# ltc4063-test.net
KiCad netlist of a schematic drawn in EAGLE
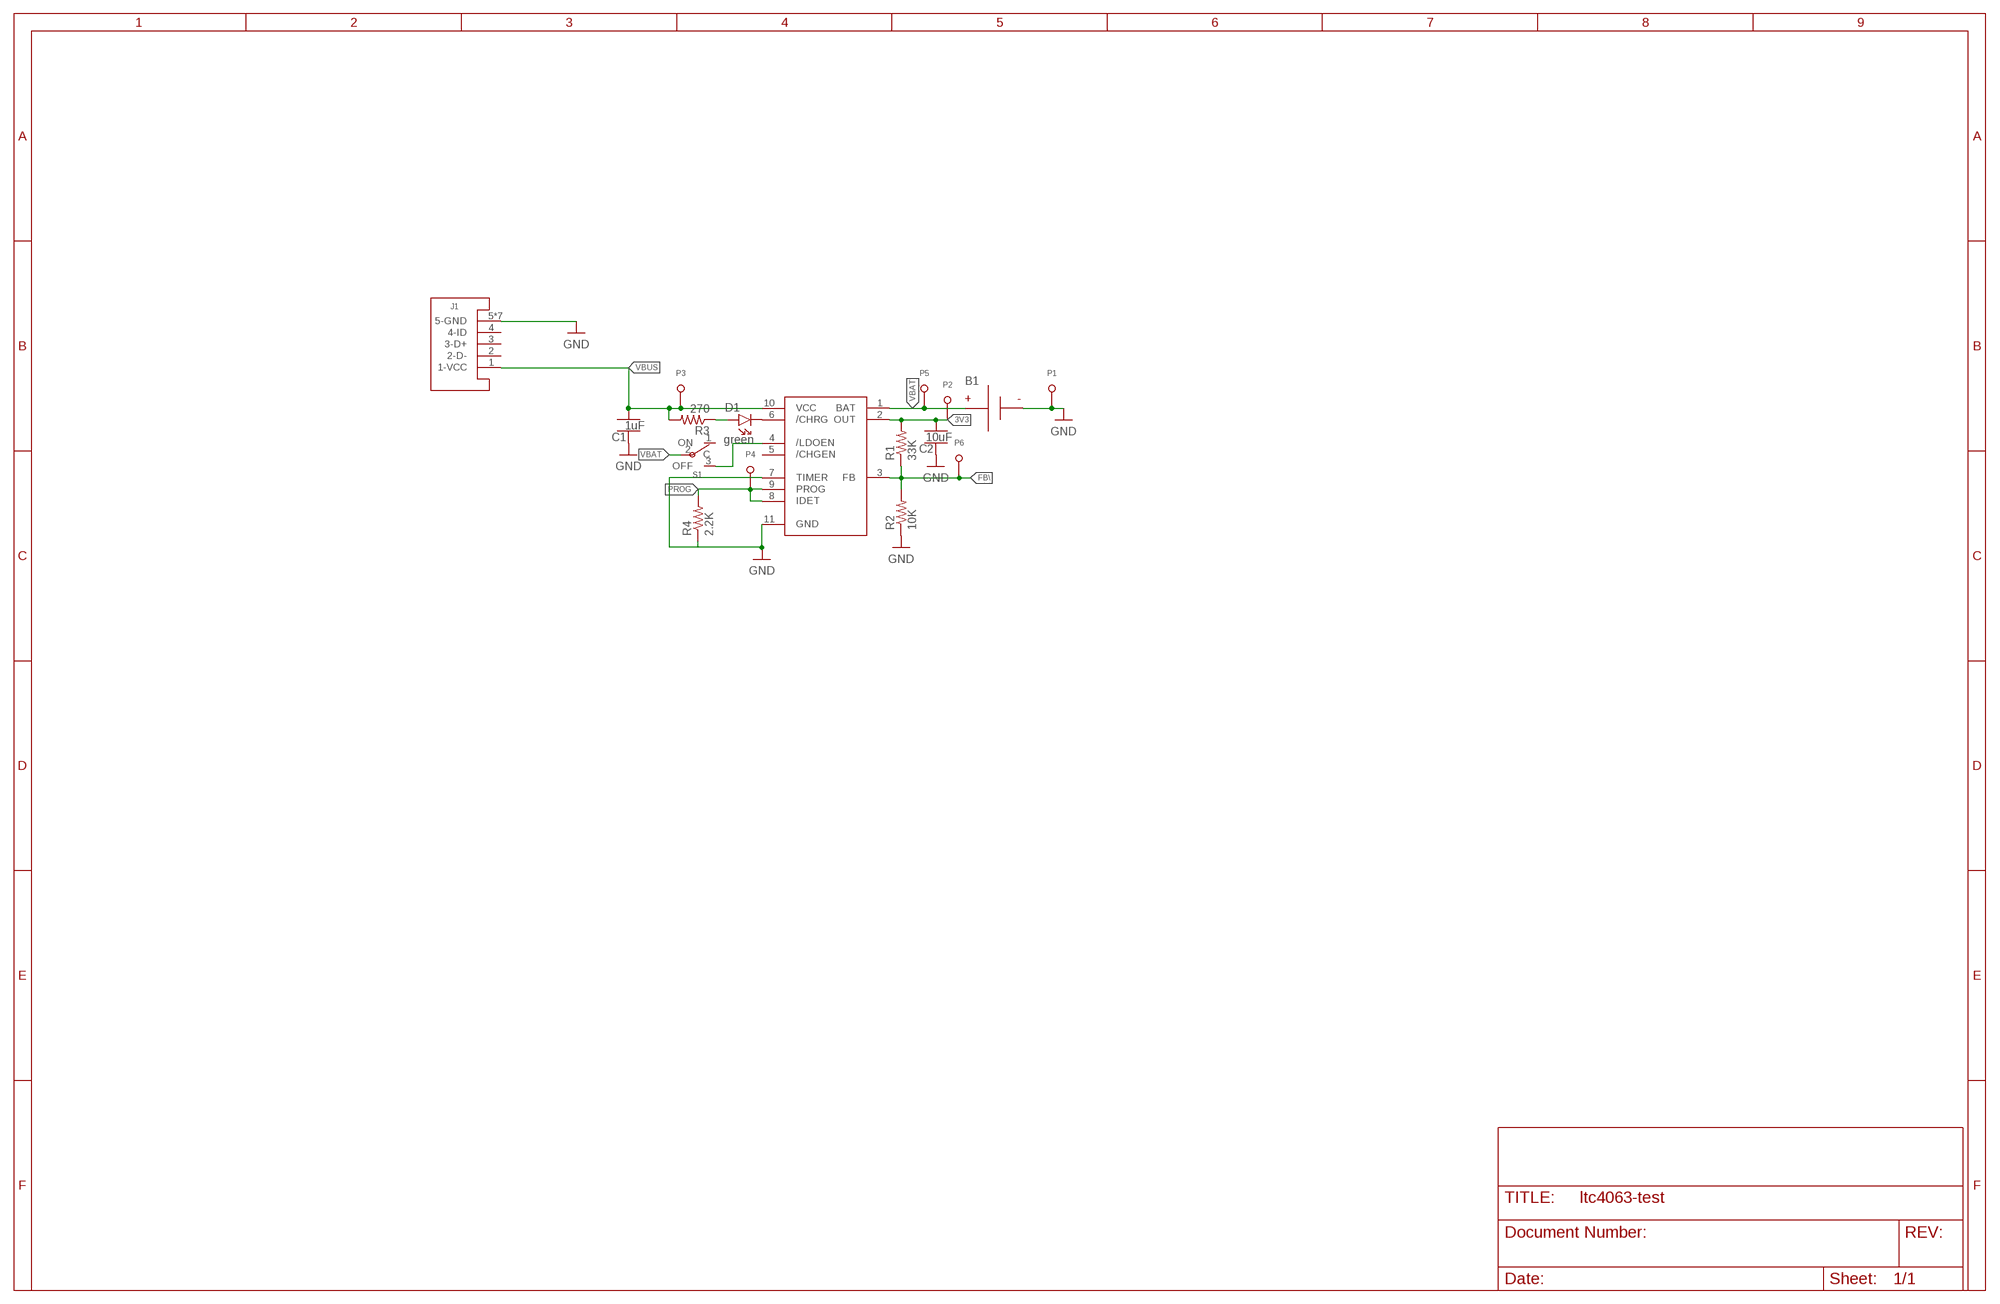
[diagram p0: schematic, sheet 1]

(export (version "E")
  (design (tool "Eeschema 10.0.6"))
  (components
    (comp (ref "B1")
      (value "BATTERY-SPRING-SMD")
      (footprint "eagle-import:WIRE-TERMINAL-1X2-2.5MM-SMD-AVX-009276002021106")
      (fields (field (name "CREATOR") "Swanson"))
      (libsource (lib "eagle-import") (part "BATTERY-SPRING-SMD"))
    )
    (comp (ref "C1")
      (value "1uF")
      (footprint "eagle-import:CAPC2012X140_HS")
      (fields
        (field (name "MFR") "Taiyo Yuden")
        (field (name "MPN") "TMK212B7105KG-T")
        (field (name "CREATOR") "Swanson")
        (field (name "REVIEWER") "Swanson")
      )
      (libsource (lib "eagle-import") (part "CAPACITOR-NP_SMD-2012-0805_CERAMIC-1UF"))
    )
    (comp (ref "C2")
      (value "10uF")
      (footprint "eagle-import:CAPC2012X140_HS")
      (fields (field (name "CREATOR") "Swanson") (field (name "REVIEWER") "Swanson"))
      (libsource (lib "eagle-import") (part "CAPACITOR-NP_SMD-2012-0805_CERAMIC-10UF"))
    )
    (comp (ref "D1")
      (value "green")
      (footprint "eagle-import:LEDSC125X200X120-2_HS")
      (fields
        (field (name "MFR") "Lite-On Inc")
        (field (name "MPN") "LTST-C170GKT")
        (field (name "CREATOR") "Swanson")
        (field (name "REVIEWER") "Swanson")
      )
      (libsource (lib "eagle-import") (part "DIODE-LED_SMD-2012-0805-GREEN"))
    )
    (comp (ref "J1")
      (value "USB-MICROA-AMPHENOL-10118192-0001LF")
      (footprint "eagle-import:USB-MICROA-10118192-0001LF")
      (fields (field (name "CREATOR") "Swanson"))
      (libsource (lib "eagle-import") (part "USB-MICROA-AMPHENOL-10118192-0001LF"))
    )
    (comp (ref "P1")
      (value "TEST-POINT")
      (footprint "eagle-import:TEST-POINT-KEYSTONE-5000")
      (fields (field (name "CREATOR") "Swanson"))
      (libsource (lib "eagle-import") (part "TEST-POINT"))
    )
    (comp (ref "P2")
      (value "TEST-POINT")
      (footprint "eagle-import:TEST-POINT-KEYSTONE-5000")
      (fields (field (name "CREATOR") "Swanson"))
      (libsource (lib "eagle-import") (part "TEST-POINT"))
    )
    (comp (ref "P3")
      (value "TEST-POINT")
      (footprint "eagle-import:TEST-POINT-KEYSTONE-5000")
      (fields (field (name "CREATOR") "Swanson"))
      (libsource (lib "eagle-import") (part "TEST-POINT"))
    )
    (comp (ref "P4")
      (value "TEST-POINT")
      (footprint "eagle-import:TEST-POINT-KEYSTONE-5000")
      (fields (field (name "CREATOR") "Swanson"))
      (libsource (lib "eagle-import") (part "TEST-POINT"))
    )
    (comp (ref "P5")
      (value "TEST-POINT")
      (footprint "eagle-import:TEST-POINT-KEYSTONE-5000")
      (fields (field (name "CREATOR") "Swanson"))
      (libsource (lib "eagle-import") (part "TEST-POINT"))
    )
    (comp (ref "P6")
      (value "TEST-POINT")
      (footprint "eagle-import:TEST-POINT-KEYSTONE-5000")
      (fields (field (name "CREATOR") "Swanson"))
      (libsource (lib "eagle-import") (part "TEST-POINT"))
    )
    (comp (ref "R1")
      (value "33K")
      (footprint "eagle-import:RESC2012X60_HS")
      (fields (field (name "CREATOR") "SWANSON"))
      (libsource (lib "eagle-import") (part "RESISTOR_SMD-2012-0805-33K"))
    )
    (comp (ref "R2")
      (value "10K")
      (footprint "eagle-import:RESC2012X60_HS")
      (fields
        (field (name "MFR") "Yageo")
        (field (name "MPN") "RC0805JR-0710KL")
        (field (name "CREATOR") "Swanson")
        (field (name "REVIEWER") "Swanson")
      )
      (libsource (lib "eagle-import") (part "RESISTOR_SMD-2012-0805-10K"))
    )
    (comp (ref "R3")
      (value "270")
      (footprint "eagle-import:RESC2012X60_HS")
      (fields (field (name "CREATOR") "SWANSON"))
      (libsource (lib "eagle-import") (part "RESISTOR_SMD-2012-0805-270"))
    )
    (comp (ref "R4")
      (value "2.2K")
      (footprint "eagle-import:RESC2012X60_HS")
      (fields (field (name "CREATOR") "SWANSON"))
      (libsource (lib "eagle-import") (part "RESISTOR_SMD-2012-0805-2.2K"))
    )
    (comp (ref "S1")
      (value "POWER-SWITCH-MFS201N-9-Z-SMD-VERTICAL")
      (footprint "eagle-import:JS102011JCQN")
      (fields (field (name "CREATOR") "Swanson"))
      (libsource (lib "eagle-import") (part "POWER-SWITCH-MFS201N-9-Z-SMD-VERTICAL"))
    )
    (comp (ref "U1")
      (value "LIPO-VREG-LTC4063")
      (footprint "eagle-import:SON50P300X300X80-11T165X238")
      (fields (field (name "CREATOR") "Swanson"))
      (libsource (lib "eagle-import") (part "LIPO-VREG-LTC4063"))
    )
  )
  (nets
    (net (code "1") (name "3V3") (class "Default")
      (node (ref "C2") (pin "2") (pinfunction "2_2") (pintype "passive"))
      (node (ref "P2") (pin "T") (pinfunction "T_T") (pintype "bidirectional"))
      (node (ref "R1") (pin "2") (pinfunction "2_2") (pintype "passive"))
      (node (ref "U1") (pin "2") (pinfunction "OUT_2") (pintype "bidirectional"))
    )
    (net (code "2") (name "FB\\") (class "Default")
      (node (ref "P6") (pin "T") (pinfunction "T_T") (pintype "bidirectional"))
      (node (ref "R1") (pin "1") (pinfunction "1_1") (pintype "passive"))
      (node (ref "R2") (pin "2") (pinfunction "2_2") (pintype "passive"))
      (node (ref "U1") (pin "3") (pinfunction "FB_3") (pintype "bidirectional"))
    )
    (net (code "3") (name "GND") (class "Default")
      (node (ref "B1") (pin "2A") (pinfunction "N_2A") (pintype "bidirectional"))
      (node (ref "B1") (pin "2B") (pinfunction "N_2B") (pintype "bidirectional"))
      (node (ref "C1") (pin "1") (pinfunction "1_1") (pintype "passive"))
      (node (ref "C2") (pin "1") (pinfunction "1_1") (pintype "passive"))
      (node (ref "J1") (pin "10") (pinfunction "5-GND_10") (pintype "bidirectional"))
      (node (ref "J1") (pin "11") (pinfunction "5-GND_11") (pintype "bidirectional"))
      (node (ref "J1") (pin "5") (pinfunction "5-GND_5") (pintype "bidirectional"))
      (node (ref "J1") (pin "6") (pinfunction "5-GND_6") (pintype "bidirectional"))
      (node (ref "J1") (pin "7") (pinfunction "5-GND_7") (pintype "bidirectional"))
      (node (ref "J1") (pin "8") (pinfunction "5-GND_8") (pintype "bidirectional"))
      (node (ref "J1") (pin "9") (pinfunction "5-GND_9") (pintype "bidirectional"))
      (node (ref "P1") (pin "T") (pinfunction "T_T") (pintype "bidirectional"))
      (node (ref "R2") (pin "1") (pinfunction "1_1") (pintype "passive"))
      (node (ref "R4") (pin "1") (pinfunction "1_1") (pintype "passive"))
      (node (ref "U1") (pin "11") (pinfunction "GND_11") (pintype "bidirectional"))
      (node (ref "U1") (pin "7") (pinfunction "TIMER_7") (pintype "bidirectional"))
    )
    (net (code "4") (name "Net-(D1-PadA)") (class "Default")
      (node (ref "D1") (pin "A") (pinfunction "A_A") (pintype "passive"))
      (node (ref "R3") (pin "1") (pinfunction "1_1") (pintype "passive"))
    )
    (net (code "5") (name "Net-(S1-OFF)") (class "Default")
      (node (ref "S1") (pin "3") (pinfunction "OFF_3") (pintype "bidirectional"))
      (node (ref "U1") (pin "4") (pinfunction "/LDOEN_4") (pintype "bidirectional"))
    )
    (net (code "6") (name "Net-(U1-{slash}CHRG)") (class "Default")
      (node (ref "D1") (pin "C") (pinfunction "C_C") (pintype "passive"))
      (node (ref "U1") (pin "6") (pinfunction "/CHRG_6") (pintype "bidirectional"))
    )
    (net (code "7") (name "PROG") (class "Default")
      (node (ref "P4") (pin "T") (pinfunction "T_T") (pintype "bidirectional"))
      (node (ref "R4") (pin "2") (pinfunction "2_2") (pintype "passive"))
      (node (ref "U1") (pin "8") (pinfunction "IDET_8") (pintype "bidirectional"))
      (node (ref "U1") (pin "9") (pinfunction "PROG_9") (pintype "bidirectional"))
    )
    (net (code "8") (name "VBAT") (class "Default")
      (node (ref "B1") (pin "1A") (pinfunction "P_1A") (pintype "bidirectional"))
      (node (ref "B1") (pin "1B") (pinfunction "P_1B") (pintype "bidirectional"))
      (node (ref "P5") (pin "T") (pinfunction "T_T") (pintype "bidirectional"))
      (node (ref "S1") (pin "2") (pinfunction "C_2") (pintype "bidirectional"))
      (node (ref "U1") (pin "1") (pinfunction "BAT_1") (pintype "bidirectional"))
    )
    (net (code "9") (name "VBUS") (class "Default")
      (node (ref "C1") (pin "2") (pinfunction "2_2") (pintype "passive"))
      (node (ref "J1") (pin "1") (pinfunction "1-VCC_1") (pintype "bidirectional"))
      (node (ref "P3") (pin "T") (pinfunction "T_T") (pintype "bidirectional"))
      (node (ref "R3") (pin "2") (pinfunction "2_2") (pintype "passive"))
      (node (ref "U1") (pin "10") (pinfunction "VCC_10") (pintype "bidirectional"))
    )
    (net (code "10") (name "unconnected-(J1-2-D--Pad2)") (class "Default")
      (node (ref "J1") (pin "2") (pinfunction "2-D-_2") (pintype "bidirectional"))
    )
    (net (code "11") (name "unconnected-(J1-3-D+-Pad3)") (class "Default")
      (node (ref "J1") (pin "3") (pinfunction "3-D+_3") (pintype "bidirectional"))
    )
    (net (code "12") (name "unconnected-(J1-4-ID-Pad4)") (class "Default")
      (node (ref "J1") (pin "4") (pinfunction "4-ID_4") (pintype "bidirectional"))
    )
    (net (code "13") (name "unconnected-(S1-ON-Pad1)") (class "Default")
      (node (ref "S1") (pin "1") (pinfunction "ON_1") (pintype "bidirectional"))
    )
    (net (code "14") (name "unconnected-(U1-{slash}CHGEN-Pad5)") (class "Default")
      (node (ref "U1") (pin "5") (pinfunction "/CHGEN_5") (pintype "bidirectional"))
    )
  )
)
